# 780-00029_rev1_Pg1_Backplane_Instrument_.net
KiCad netlist of a schematic drawn in Altium Designer
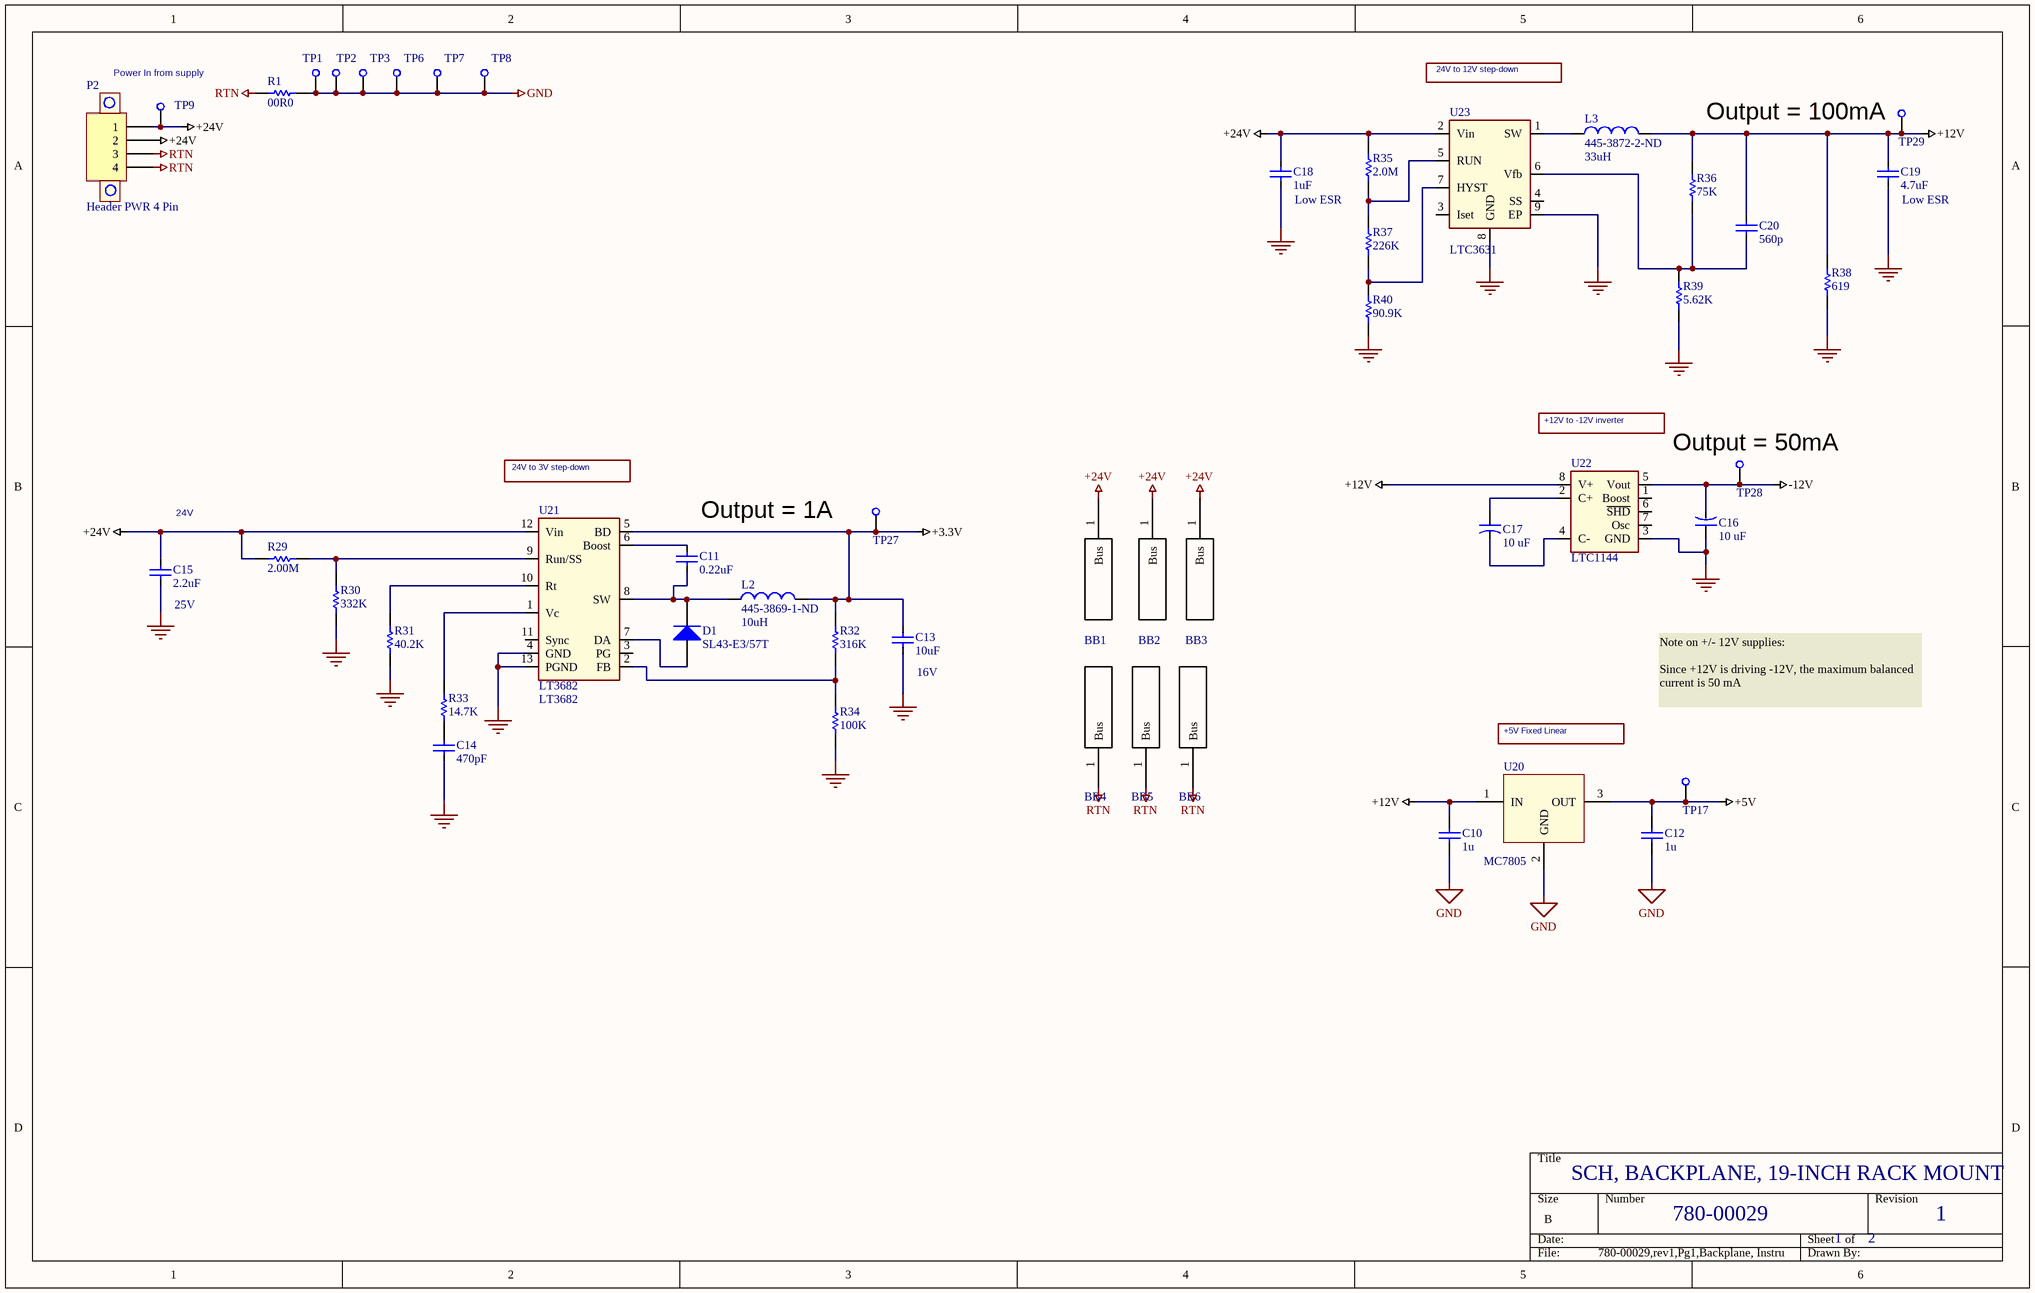
[diagram p0: 780-00029,rev1,Pg1,Backplane, Instrument Crate.SchDoc]

(export (version "E")
  (design (tool "Eeschema 10.0.6"))
  (components
    (comp (ref "BB1")
      (value "Bus Bar")
      (footprint "Bus Bar 1.5\" pitch")
      (fields (field (name "MANUFACTURER") "Circuit Components Inc."))
      (libsource (lib "Richs Schematic Components") (part "Bus Bar"))
    )
    (comp (ref "BB2")
      (value "Bus Bar")
      (footprint "Bus Bar 1.5\" pitch")
      (fields (field (name "MANUFACTURER") "Circuit Components Inc."))
      (libsource (lib "Richs Schematic Components") (part "Bus Bar"))
    )
    (comp (ref "BB3")
      (value "Bus Bar")
      (footprint "Bus Bar 1.5\" pitch")
      (fields (field (name "MANUFACTURER") "Circuit Components Inc."))
      (libsource (lib "Richs Schematic Components") (part "Bus Bar"))
    )
    (comp (ref "BB4")
      (value "Bus Bar")
      (footprint "Bus Bar 1.5\" pitch")
      (fields (field (name "MANUFACTURER") "Circuit Components Inc."))
      (libsource (lib "Richs Schematic Components") (part "Bus Bar"))
    )
    (comp (ref "BB5")
      (value "Bus Bar")
      (footprint "Bus Bar 1.5\" pitch")
      (fields (field (name "MANUFACTURER") "Circuit Components Inc."))
      (libsource (lib "Richs Schematic Components") (part "Bus Bar"))
    )
    (comp (ref "BB6")
      (value "Bus Bar")
      (footprint "Bus Bar 1.5\" pitch")
      (fields (field (name "MANUFACTURER") "Circuit Components Inc."))
      (libsource (lib "Richs Schematic Components") (part "Bus Bar"))
    )
    (comp (ref "C10")
      (value "1u")
      (footprint "2012[0805]")
      (description "Capacitor")
      (fields (field (name "MANUFACTURER") "Taiyo Yuden"))
      (libsource (lib "Miscellaneous Devices") (part "Cap"))
    )
    (comp (ref "C11")
      (value "0.22uF")
      (footprint "SMD_0805")
      (description "Capacitor")
      (fields (field (name "Comment") "Cap SMD"))
      (libsource (lib "Richs Schematic Components") (part "Cap SMD"))
    )
    (comp (ref "C12")
      (value "1u")
      (footprint "2012[0805]")
      (description "Capacitor")
      (fields (field (name "MANUFACTURER") "Taiyo Yuden"))
      (libsource (lib "Miscellaneous Devices") (part "Cap"))
    )
    (comp (ref "C13")
      (value "16V")
      (footprint "SMD_0805")
      (description "Capacitor")
      (fields (field (name "ALTIUM_VALUE") "10uF"))
      (libsource (lib "Richs Schematic Components") (part "Cap SMD"))
    )
    (comp (ref "C14")
      (value "470pF")
      (footprint "SMD_0805")
      (description "Capacitor")
      (fields (field (name "Comment") "Cap SMD"))
      (libsource (lib "Richs Schematic Components") (part "Cap SMD"))
    )
    (comp (ref "C15")
      (value "25V")
      (footprint "SMD_0805")
      (description "Capacitor")
      (fields (field (name "MANUFACTURER") "Taiyo Yuden") (field (name "ALTIUM_VALUE") "2.2uF"))
      (libsource (lib "Richs Schematic Components") (part "Cap SMD"))
    )
    (comp (ref "C16")
      (value "10 uF")
      (footprint "SMD_CAP_3216")
      (description "outline 3.2mm x 1.6mm")
      (fields (field (name "MANUFACTURER") "KEMET") (field (name "Comment") "16V"))
      (libsource (lib "Richs Schematic Components") (part "Cap Tant 16V"))
    )
    (comp (ref "C17")
      (value "10 uF")
      (footprint "SMD_CAP_3216")
      (description "outline 3.2mm x 1.6mm")
      (fields (field (name "MANUFACTURER") "KEMET") (field (name "Comment") "16V"))
      (libsource (lib "Richs Schematic Components") (part "Cap Tant 16V"))
    )
    (comp (ref "C18")
      (value "Low ESR")
      (footprint "SMD_1206")
      (description "Capacitor")
      (fields (field (name "MANUFACTURER") "TDK") (field (name "ALTIUM_VALUE") "1uF"))
      (libsource (lib "Richs Schematic Components") (part "Cap SMD"))
    )
    (comp (ref "C19")
      (value "Low ESR")
      (footprint "SMD_1206")
      (description "Capacitor")
      (fields (field (name "MANUFACTURER") "TDK") (field (name "ALTIUM_VALUE") "4.7uF"))
      (libsource (lib "Richs Schematic Components") (part "Cap SMD"))
    )
    (comp (ref "C20")
      (value "560p")
      (footprint "SMD_0805")
      (description "Capacitor")
      (fields (field (name "Comment") "Cap SMD"))
      (libsource (lib "Richs Schematic Components") (part "Cap SMD"))
    )
    (comp (ref "D1")
      (value "SL43-E3/57T")
      (footprint "DO-214AB")
      (description "Default Diode")
      (fields (field (name "MANUFACTURER") "Vishay/Dale"))
      (libsource (lib "Miscellaneous Devices") (part "Diode"))
    )
    (comp (ref "L2")
      (value "445-3869-1-ND")
      (footprint "Inductor TDC SLF")
      (description "Inductor")
      (fields (field (name "MANUFACTURER") "TDK") (field (name "ALTIUM_VALUE") "10uH"))
      (libsource (lib "Richs Schematic Components") (part "Inductor SMD 10uH 1.8A"))
    )
    (comp (ref "L3")
      (value "445-3872-2-ND")
      (footprint "Inductor TDC SLF")
      (description "Inductor")
      (fields (field (name "MANUFACTURER") "TDK") (field (name "ALTIUM_VALUE") "33uH"))
      (libsource (lib "Richs Schematic Components") (part "Inductor SMD 10uH 1.8A"))
    )
    (comp (ref "P2")
      (value "Header PWR 4 Pin")
      (footprint "HDR-4 pin w/screw")
      (description "Header, 4-Pin")
      (fields (field (name "MANUFACTURER") "tyco"))
      (libsource (lib "Richs Schematic Components") (part "Header 4 PWR"))
    )
    (comp (ref "R1")
      (value "00R0")
      (footprint "SMD_0805")
      (description "Resistor 0805")
      (fields (field (name "MANUFACTURER") "Vishay/Dale") (field (name "Comment") "Res 0805"))
      (libsource (lib "Richs Schematic Components") (part "Res SMD"))
    )
    (comp (ref "R29")
      (value "2.00M")
      (footprint "SMD_0805")
      (description "Resistor 0805")
      (fields (field (name "MANUFACTURER") "Vishay/Dale") (field (name "Comment") "Res 0805"))
      (libsource (lib "Richs Schematic Components") (part "Res SMD"))
    )
    (comp (ref "R30")
      (value "332K")
      (footprint "SMD_0805")
      (description "Resistor 0805")
      (fields (field (name "MANUFACTURER") "Vishay/Dale") (field (name "Comment") "Res 0805"))
      (libsource (lib "Richs Schematic Components") (part "Res SMD"))
    )
    (comp (ref "R31")
      (value "40.2K")
      (footprint "SMD_0805")
      (description "Resistor 0805")
      (fields (field (name "MANUFACTURER") "Vishay/Dale") (field (name "Comment") "Res 0805"))
      (libsource (lib "Richs Schematic Components") (part "Res SMD"))
    )
    (comp (ref "R32")
      (value "316K")
      (footprint "SMD_0805")
      (description "Resistor 0805")
      (fields (field (name "MANUFACTURER") "Vishay/Dale") (field (name "Comment") "Res 0805"))
      (libsource (lib "Richs Schematic Components") (part "Res SMD"))
    )
    (comp (ref "R33")
      (value "14.7K")
      (footprint "SMD_0805")
      (description "Resistor 0805")
      (fields (field (name "MANUFACTURER") "Vishay/Dale") (field (name "Comment") "Res 0805"))
      (libsource (lib "Richs Schematic Components") (part "Res SMD"))
    )
    (comp (ref "R34")
      (value "100K")
      (footprint "SMD_0805")
      (description "Resistor 0805")
      (fields (field (name "MANUFACTURER") "Vishay/Dale") (field (name "Comment") "Res 0805"))
      (libsource (lib "Richs Schematic Components") (part "Res SMD"))
    )
    (comp (ref "R35")
      (value "2.0M")
      (footprint "SMD_0805")
      (description "Resistor 0805")
      (fields (field (name "MANUFACTURER") "Vishay/Dale") (field (name "Comment") "Res 0805"))
      (libsource (lib "Richs Schematic Components") (part "Res SMD"))
    )
    (comp (ref "R36")
      (value "75K")
      (footprint "SMD_0805")
      (description "Resistor 0805")
      (fields (field (name "MANUFACTURER") "Vishay/Dale") (field (name "Comment") "Res 0805"))
      (libsource (lib "Richs Schematic Components") (part "Res SMD"))
    )
    (comp (ref "R37")
      (value "226K")
      (footprint "SMD_0805")
      (description "Resistor 0805")
      (fields (field (name "MANUFACTURER") "Vishay/Dale") (field (name "Comment") "Res 0805"))
      (libsource (lib "Richs Schematic Components") (part "Res SMD"))
    )
    (comp (ref "R38")
      (value "619")
      (footprint "SMD_0805")
      (description "Resistor 0805")
      (fields (field (name "MANUFACTURER") "Vishay/Dale") (field (name "Comment") "Res 0805"))
      (libsource (lib "Richs Schematic Components") (part "Res SMD"))
    )
    (comp (ref "R39")
      (value "5.62K")
      (footprint "SMD_0805")
      (description "Resistor 0805")
      (fields (field (name "MANUFACTURER") "Vishay/Dale") (field (name "Comment") "Res 0805"))
      (libsource (lib "Richs Schematic Components") (part "Res SMD"))
    )
    (comp (ref "R40")
      (value "90.9K")
      (footprint "SMD_0805")
      (description "Resistor 0805")
      (fields (field (name "MANUFACTURER") "Vishay/Dale") (field (name "Comment") "Res 0805"))
      (libsource (lib "Richs Schematic Components") (part "Res SMD"))
    )
    (comp (ref "TP1")
      (value "Test point")
      (footprint "Protel 99SE BANKS PCB:PAD_80D_052H")
      (description "Test Point")
      (fields (field (name "MANUFACTURER") "Keystone"))
      (libsource (lib "Richs Schematic Components") (part "Test point"))
    )
    (comp (ref "TP2")
      (value "Test point")
      (footprint "Protel 99SE BANKS PCB:PAD_80D_052H")
      (description "Test Point")
      (fields (field (name "MANUFACTURER") "Keystone"))
      (libsource (lib "Richs Schematic Components") (part "Test point"))
    )
    (comp (ref "TP3")
      (value "Test point")
      (footprint "Protel 99SE BANKS PCB:PAD_80D_052H")
      (description "Test Point")
      (fields (field (name "MANUFACTURER") "Keystone"))
      (libsource (lib "Richs Schematic Components") (part "Test point"))
    )
    (comp (ref "TP6")
      (value "Test point")
      (footprint "Protel 99SE BANKS PCB:PAD_80D_052H")
      (description "Test Point")
      (fields (field (name "MANUFACTURER") "Keystone"))
      (libsource (lib "Richs Schematic Components") (part "Test point"))
    )
    (comp (ref "TP7")
      (value "Test point")
      (footprint "Protel 99SE BANKS PCB:PAD_80D_052H")
      (description "Test Point")
      (fields (field (name "MANUFACTURER") "Keystone"))
      (libsource (lib "Richs Schematic Components") (part "Test point"))
    )
    (comp (ref "TP8")
      (value "Test point")
      (footprint "Protel 99SE BANKS PCB:PAD_80D_052H")
      (description "Test Point")
      (fields (field (name "MANUFACTURER") "Keystone"))
      (libsource (lib "Richs Schematic Components") (part "Test point"))
    )
    (comp (ref "TP9")
      (value "Test Point SMD")
      (footprint "SMD_TEST POINT")
      (description "SMD loop test point")
      (libsource (lib "Richs Schematic Components") (part "Test Point SMD"))
    )
    (comp (ref "TP17")
      (value "Test Point SMD")
      (footprint "SMD_TEST POINT")
      (description "SMD loop test point")
      (libsource (lib "Richs Schematic Components") (part "Test Point SMD"))
    )
    (comp (ref "TP27")
      (value "Test Point SMD")
      (footprint "SMD_TEST POINT")
      (description "SMD loop test point")
      (libsource (lib "Richs Schematic Components") (part "Test Point SMD"))
    )
    (comp (ref "TP28")
      (value "Test Point SMD")
      (footprint "SMD_TEST POINT")
      (description "SMD loop test point")
      (libsource (lib "Richs Schematic Components") (part "Test Point SMD"))
    )
    (comp (ref "TP29")
      (value "Test Point SMD")
      (footprint "SMD_TEST POINT")
      (description "SMD loop test point")
      (libsource (lib "Richs Schematic Components") (part "Test Point SMD"))
    )
    (comp (ref "U20")
      (value "MC7805")
      (footprint "TO-252(D-PAK)  PowerPAD")
      (description "MC78M05")
      (fields (field (name "MANUFACTURER") "Fairchild") (field (name "Comment") "Voltage Reg, Fixed"))
      (libsource (lib "Richs Schematic Components") (part "Voltage Reg, Fixed"))
    )
    (comp (ref "U21")
      (value "LT3682")
      (footprint "DD12/DFN12")
      (description "1A uPwr Step-Down switching regulator")
      (fields (field (name "MANUFACTURER") "Linear") (field (name "ALTIUM_VALUE") "LT3682"))
      (libsource (lib "Richs Schematic Components") (part "LT3682"))
    )
    (comp (ref "U22")
      (value "LTC1144")
      (footprint "S8_M")
      (description "IC VOLT CONV SW-CAP W/SHTDN8SOIC")
      (fields (field (name "MANUFACTURER") "Linear"))
      (libsource (lib "Richs Schematic Components") (part "LTC1144"))
    )
    (comp (ref "U23")
      (value "LTC3631")
      (footprint "DD8/DFN8")
      (description "IC CONV STP-DWN ADJ 8-DFN")
      (fields (field (name "MANUFACTURER") "Linear"))
      (libsource (lib "Richs Schematic Components") (part "LTC3631"))
    )
  )
  (nets
    (net (code "1") (name "+3.3V") (class "Default")
      (node (ref "C13") (pin "2") (pinfunction "2_2") (pintype "passive"))
      (node (ref "L2") (pin "2") (pinfunction "2_2") (pintype "passive"))
      (node (ref "R32") (pin "2") (pinfunction "2_2") (pintype "passive"))
      (node (ref "TP27") (pin "1") (pinfunction "TP_1") (pintype "passive"))
      (node (ref "U21") (pin "5") (pinfunction "BD_5") (pintype "passive"))
    )
    (net (code "2") (name "+5V") (class "Default")
      (node (ref "C12") (pin "1") (pinfunction "1_1") (pintype "passive"))
      (node (ref "TP17") (pin "1") (pinfunction "TP_1") (pintype "passive"))
      (node (ref "U20") (pin "3") (pinfunction "OUT_3") (pintype "passive"))
    )
    (net (code "3") (name "+12V") (class "Default")
      (node (ref "C10") (pin "1") (pinfunction "1_1") (pintype "passive"))
      (node (ref "C19") (pin "2") (pinfunction "2_2") (pintype "passive"))
      (node (ref "C20") (pin "2") (pinfunction "2_2") (pintype "passive"))
      (node (ref "L3") (pin "2") (pinfunction "2_2") (pintype "passive"))
      (node (ref "R36") (pin "2") (pinfunction "2_2") (pintype "passive"))
      (node (ref "R38") (pin "2") (pinfunction "2_2") (pintype "passive"))
      (node (ref "TP29") (pin "1") (pinfunction "TP_1") (pintype "passive"))
      (node (ref "U20") (pin "1") (pinfunction "IN_1") (pintype "passive"))
      (node (ref "U22") (pin "8") (pinfunction "V+_8") (pintype "power_in"))
    )
    (net (code "4") (name "+24V") (class "Default")
      (node (ref "BB1") (pin "1") (pinfunction "Bus_1") (pintype "passive"))
      (node (ref "BB2") (pin "1") (pinfunction "Bus_1") (pintype "passive"))
      (node (ref "BB3") (pin "1") (pinfunction "Bus_1") (pintype "passive"))
      (node (ref "C15") (pin "2") (pinfunction "2_2") (pintype "passive"))
      (node (ref "C18") (pin "2") (pinfunction "2_2") (pintype "passive"))
      (node (ref "P2") (pin "1") (pinfunction "1_1") (pintype "passive"))
      (node (ref "P2") (pin "2") (pinfunction "2_2") (pintype "passive"))
      (node (ref "R29") (pin "1") (pinfunction "1_1") (pintype "passive"))
      (node (ref "R35") (pin "2") (pinfunction "2_2") (pintype "passive"))
      (node (ref "TP9") (pin "1") (pinfunction "TP_1") (pintype "passive"))
      (node (ref "U21") (pin "12") (pinfunction "Vin_12") (pintype "passive"))
      (node (ref "U23") (pin "2") (pinfunction "Vin_2") (pintype "passive"))
    )
    (net (code "5") (name "-12V") (class "Default")
      (node (ref "C16") (pin "2") (pinfunction "2_2") (pintype "passive"))
      (node (ref "TP28") (pin "1") (pinfunction "TP_1") (pintype "passive"))
      (node (ref "U22") (pin "5") (pinfunction "Vout_5") (pintype "passive"))
    )
    (net (code "6") (name "GND") (class "Default")
      (node (ref "C10") (pin "2") (pinfunction "2_2") (pintype "passive"))
      (node (ref "C12") (pin "2") (pinfunction "2_2") (pintype "passive"))
      (node (ref "C13") (pin "1") (pinfunction "1_1") (pintype "passive"))
      (node (ref "C14") (pin "1") (pinfunction "1_1") (pintype "passive"))
      (node (ref "C15") (pin "1") (pinfunction "1_1") (pintype "passive"))
      (node (ref "C16") (pin "1") (pinfunction "1_1") (pintype "passive"))
      (node (ref "C18") (pin "1") (pinfunction "1_1") (pintype "passive"))
      (node (ref "C19") (pin "1") (pinfunction "1_1") (pintype "passive"))
      (node (ref "R1") (pin "2") (pinfunction "2_2") (pintype "passive"))
      (node (ref "R30") (pin "1") (pinfunction "1_1") (pintype "passive"))
      (node (ref "R31") (pin "1") (pinfunction "1_1") (pintype "passive"))
      (node (ref "R34") (pin "1") (pinfunction "1_1") (pintype "passive"))
      (node (ref "R38") (pin "1") (pinfunction "1_1") (pintype "passive"))
      (node (ref "R39") (pin "1") (pinfunction "1_1") (pintype "passive"))
      (node (ref "R40") (pin "1") (pinfunction "1_1") (pintype "passive"))
      (node (ref "TP1") (pin "1") (pinfunction "TP_1") (pintype "passive"))
      (node (ref "TP2") (pin "1") (pinfunction "TP_1") (pintype "passive"))
      (node (ref "TP3") (pin "1") (pinfunction "TP_1") (pintype "passive"))
      (node (ref "TP6") (pin "1") (pinfunction "TP_1") (pintype "passive"))
      (node (ref "TP7") (pin "1") (pinfunction "TP_1") (pintype "passive"))
      (node (ref "TP8") (pin "1") (pinfunction "TP_1") (pintype "passive"))
      (node (ref "U20") (pin "2") (pinfunction "GND_2") (pintype "passive"))
      (node (ref "U21") (pin "13") (pinfunction "PGND_13") (pintype "passive"))
      (node (ref "U21") (pin "4") (pinfunction "GND_4") (pintype "power_in"))
      (node (ref "U22") (pin "3") (pinfunction "GND_3") (pintype "passive"))
      (node (ref "U23") (pin "8") (pinfunction "GND_8") (pintype "passive"))
      (node (ref "U23") (pin "9") (pinfunction "EP_9") (pintype "passive"))
    )
    (net (code "7") (name "Net-(C14-Pad2)") (class "Default")
      (node (ref "C14") (pin "2") (pinfunction "2_2") (pintype "passive"))
      (node (ref "R33") (pin "1") (pinfunction "1_1") (pintype "passive"))
    )
    (net (code "8") (name "Net-(D1-A)") (class "Default")
      (node (ref "D1") (pin "1") (pinfunction "A_1") (pintype "passive"))
      (node (ref "U21") (pin "7") (pinfunction "DA_7") (pintype "passive"))
    )
    (net (code "9") (name "Net-(D1-K)") (class "Default")
      (node (ref "C11") (pin "1") (pinfunction "1_1") (pintype "passive"))
      (node (ref "D1") (pin "2") (pinfunction "K_2") (pintype "passive"))
      (node (ref "L2") (pin "1") (pinfunction "1_1") (pintype "passive"))
      (node (ref "U21") (pin "8") (pinfunction "SW_8") (pintype "passive"))
    )
    (net (code "10") (name "Net-(U21-Boost)") (class "Default")
      (node (ref "C11") (pin "2") (pinfunction "2_2") (pintype "passive"))
      (node (ref "U21") (pin "6") (pinfunction "Boost_6") (pintype "passive"))
    )
    (net (code "11") (name "Net-(U21-FB)") (class "Default")
      (node (ref "R32") (pin "1") (pinfunction "1_1") (pintype "passive"))
      (node (ref "R34") (pin "2") (pinfunction "2_2") (pintype "passive"))
      (node (ref "U21") (pin "2") (pinfunction "FB_2") (pintype "passive"))
    )
    (net (code "12") (name "Net-(U21-Rt)") (class "Default")
      (node (ref "R31") (pin "2") (pinfunction "2_2") (pintype "passive"))
      (node (ref "U21") (pin "10") (pinfunction "Rt_10") (pintype "passive"))
    )
    (net (code "13") (name "Net-(U21-Run{slash}SS)") (class "Default")
      (node (ref "R29") (pin "2") (pinfunction "2_2") (pintype "passive"))
      (node (ref "R30") (pin "2") (pinfunction "2_2") (pintype "passive"))
      (node (ref "U21") (pin "9") (pinfunction "Run/SS_9") (pintype "passive"))
    )
    (net (code "14") (name "Net-(U21-Vc)") (class "Default")
      (node (ref "R33") (pin "2") (pinfunction "2_2") (pintype "passive"))
      (node (ref "U21") (pin "1") (pinfunction "Vc_1") (pintype "passive"))
    )
    (net (code "15") (name "Net-(U22-C+)") (class "Default")
      (node (ref "C17") (pin "1") (pinfunction "1_1") (pintype "passive"))
      (node (ref "U22") (pin "2") (pinfunction "C+_2") (pintype "passive"))
    )
    (net (code "16") (name "Net-(U22-C-)") (class "Default")
      (node (ref "C17") (pin "2") (pinfunction "2_2") (pintype "passive"))
      (node (ref "U22") (pin "4") (pinfunction "C-_4") (pintype "passive"))
    )
    (net (code "17") (name "Net-(U23-HYST)") (class "Default")
      (node (ref "R37") (pin "1") (pinfunction "1_1") (pintype "passive"))
      (node (ref "R40") (pin "2") (pinfunction "2_2") (pintype "passive"))
      (node (ref "U23") (pin "7") (pinfunction "HYST_7") (pintype "passive"))
    )
    (net (code "18") (name "Net-(U23-RUN)") (class "Default")
      (node (ref "R35") (pin "1") (pinfunction "1_1") (pintype "passive"))
      (node (ref "R37") (pin "2") (pinfunction "2_2") (pintype "passive"))
      (node (ref "U23") (pin "5") (pinfunction "RUN_5") (pintype "passive"))
    )
    (net (code "19") (name "Net-(U23-SW)") (class "Default")
      (node (ref "L3") (pin "1") (pinfunction "1_1") (pintype "passive"))
      (node (ref "U23") (pin "1") (pinfunction "SW_1") (pintype "passive"))
    )
    (net (code "20") (name "Net-(U23-Vfb)") (class "Default")
      (node (ref "C20") (pin "1") (pinfunction "1_1") (pintype "passive"))
      (node (ref "R36") (pin "1") (pinfunction "1_1") (pintype "passive"))
      (node (ref "R39") (pin "2") (pinfunction "2_2") (pintype "passive"))
      (node (ref "U23") (pin "6") (pinfunction "Vfb_6") (pintype "passive"))
    )
    (net (code "21") (name "RTN") (class "Default")
      (node (ref "BB4") (pin "1") (pinfunction "Bus_1") (pintype "passive"))
      (node (ref "BB5") (pin "1") (pinfunction "Bus_1") (pintype "passive"))
      (node (ref "BB6") (pin "1") (pinfunction "Bus_1") (pintype "passive"))
      (node (ref "P2") (pin "3") (pinfunction "3_3") (pintype "passive"))
      (node (ref "P2") (pin "4") (pinfunction "4_4") (pintype "passive"))
      (node (ref "R1") (pin "1") (pinfunction "1_1") (pintype "passive"))
    )
    (net (code "22") (name "unconnected-(U21-PG-Pad3)") (class "Default")
      (node (ref "U21") (pin "3") (pinfunction "PG_3") (pintype "passive"))
    )
    (net (code "23") (name "unconnected-(U21-Sync-Pad11)") (class "Default")
      (node (ref "U21") (pin "11") (pinfunction "Sync_11") (pintype "passive"))
    )
    (net (code "24") (name "unconnected-(U22-Boost-Pad1)") (class "Default")
      (node (ref "U22") (pin "1") (pinfunction "Boost_1") (pintype "passive"))
    )
    (net (code "25") (name "unconnected-(U22-Osc-Pad7)") (class "Default")
      (node (ref "U22") (pin "7") (pinfunction "Osc_7") (pintype "passive"))
    )
    (net (code "26") (name "unconnected-(U22-~{SHD}-Pad6)") (class "Default")
      (node (ref "U22") (pin "6") (pinfunction "~{SHD}_6") (pintype "passive"))
    )
    (net (code "27") (name "unconnected-(U23-Iset-Pad3)") (class "Default")
      (node (ref "U23") (pin "3") (pinfunction "Iset_3") (pintype "passive"))
    )
    (net (code "28") (name "unconnected-(U23-SS-Pad4)") (class "Default")
      (node (ref "U23") (pin "4") (pinfunction "SS_4") (pintype "passive"))
    )
  )
)
